# Shockley_EPS-v_2_0.net
KiCad netlist of a schematic drawn in EAGLE
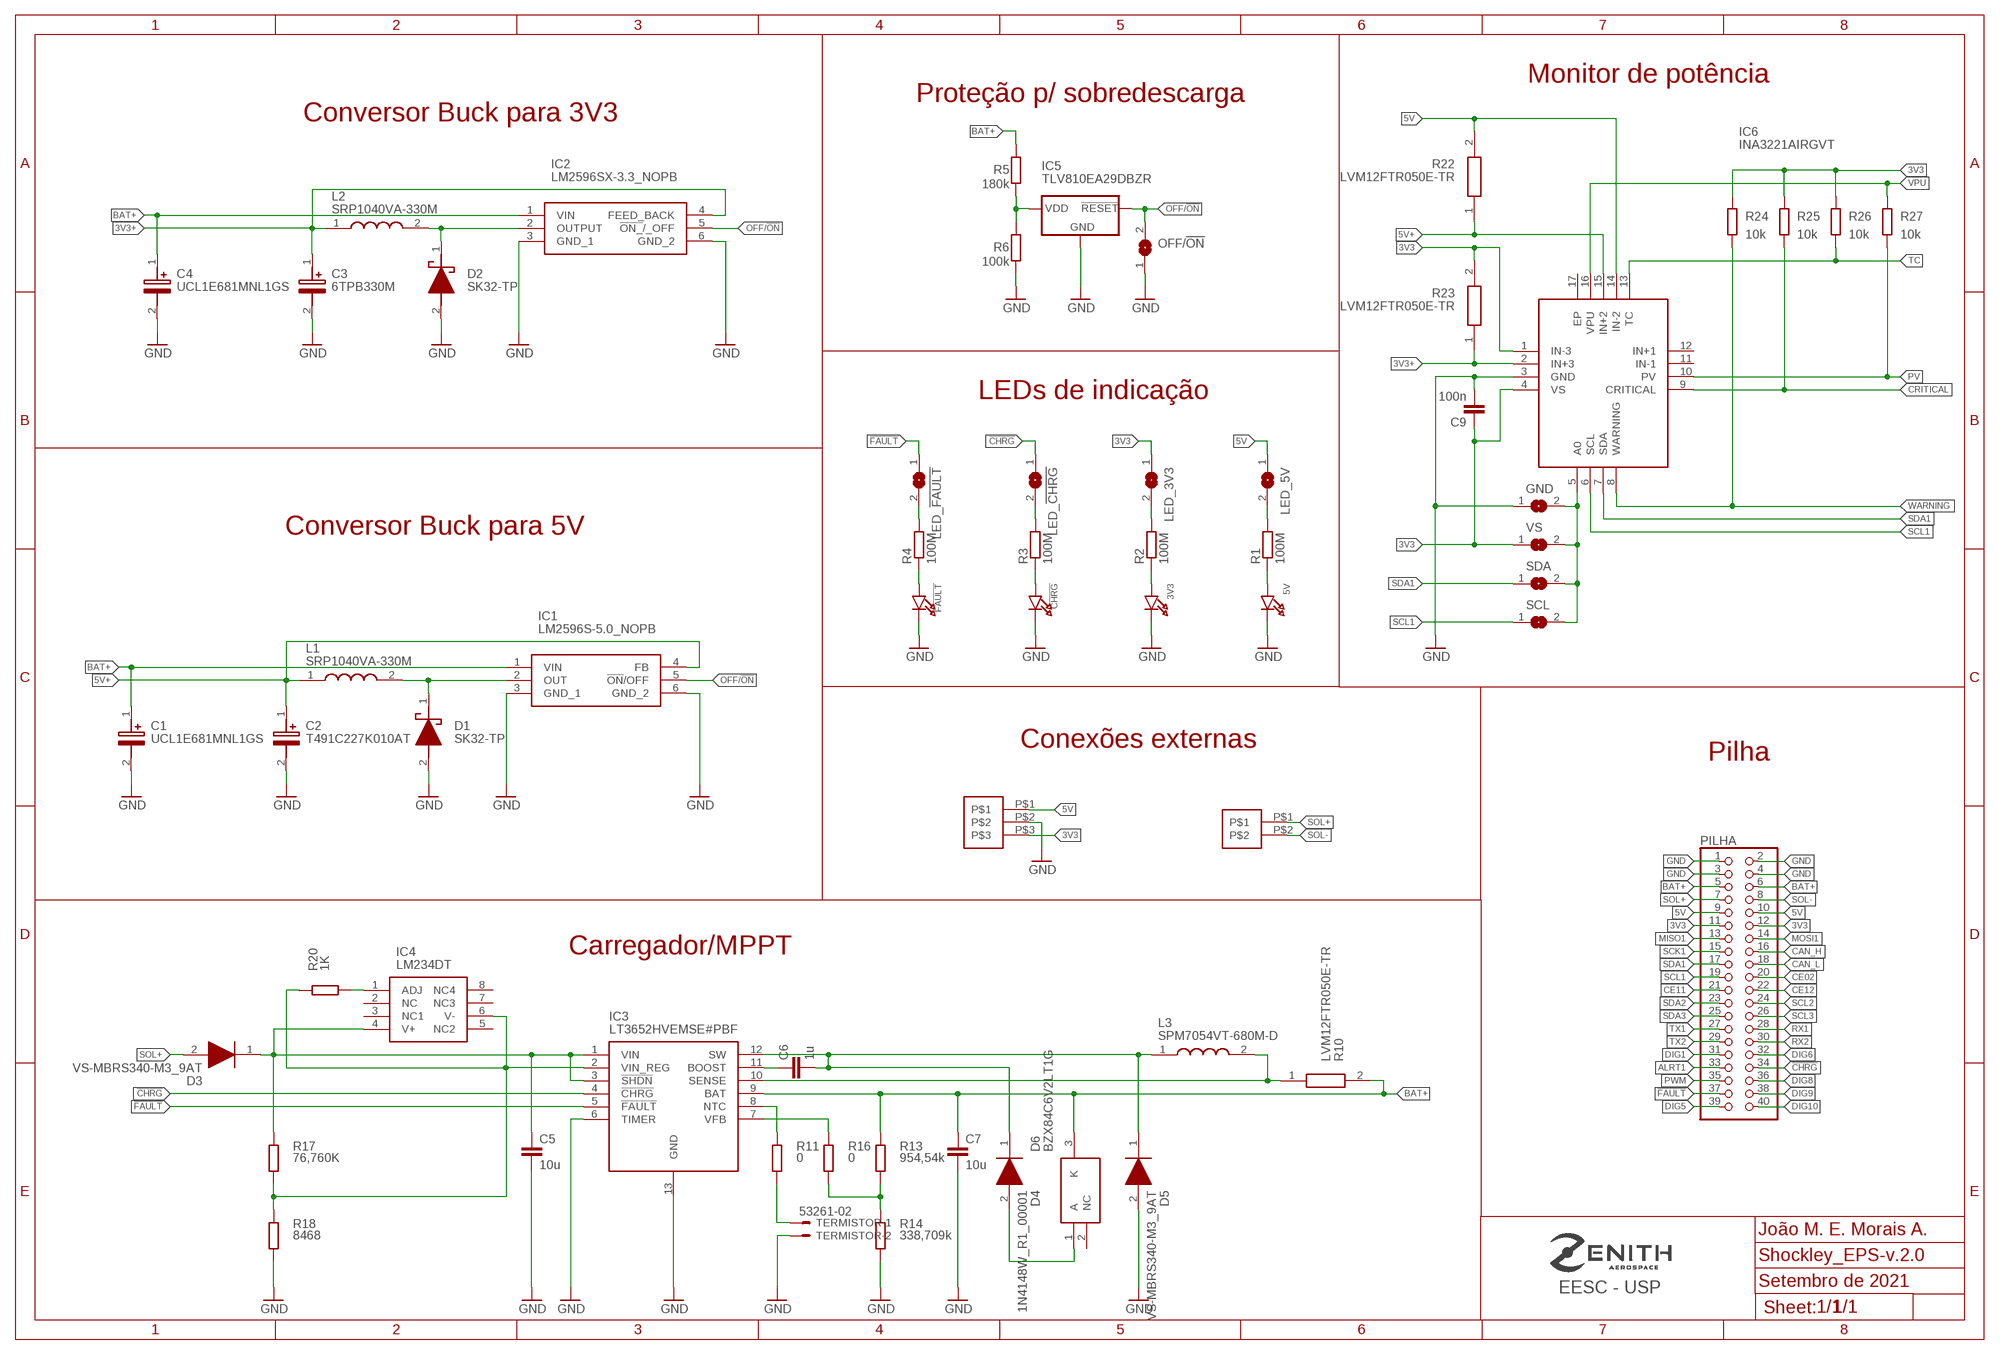
[diagram p0: schematic, sheet 1]

(export (version "E")
  (design (tool "Eeschema 10.0.6"))
  (components
    (comp (ref "!CHRG")
      (value "LED1206")
      (footprint "eagle-import:CHIPLED_1206")
      (libsource (lib "eagle-import") (part "LED1206"))
    )
    (comp (ref "!FAULT")
      (value "LED1206")
      (footprint "eagle-import:CHIPLED_1206")
      (libsource (lib "eagle-import") (part "LED1206"))
    )
    (comp (ref "3V3")
      (value "LED1206")
      (footprint "eagle-import:CHIPLED_1206")
      (libsource (lib "eagle-import") (part "LED1206"))
    )
    (comp (ref "5V")
      (value "LED1206")
      (footprint "eagle-import:CHIPLED_1206")
      (libsource (lib "eagle-import") (part "LED1206"))
    )
    (comp (ref "C1")
      (value "UCL1E681MNL1GS")
      (footprint "eagle-import:CAPAE1030X1400N")
      (fields (field (name "MOUSER_PART_NUMBER") "647-UCL1E681MNL1GS"))
      (libsource (lib "eagle-import") (part "UCL1E681MNL1GS"))
    )
    (comp (ref "C2")
      (value "T491C227K010AT")
      (footprint "eagle-import:CAPPM6032X280N")
      (fields (field (name "MOUSER_PART_NUMBER") "80-T491C227K010AT"))
      (libsource (lib "eagle-import") (part "T491C227K010AT"))
    )
    (comp (ref "C3")
      (value "6TPB330M")
      (footprint "eagle-import:10TPF150ML")
      (fields (field (name "MOUSER_PART_NUMBER") "667-6TPB330M"))
      (libsource (lib "eagle-import") (part "6TPB330M"))
    )
    (comp (ref "C4")
      (value "UCL1E681MNL1GS")
      (footprint "eagle-import:CAPAE1030X1400N")
      (fields (field (name "MOUSER_PART_NUMBER") "647-UCL1E681MNL1GS"))
      (libsource (lib "eagle-import") (part "UCL1E681MNL1GS"))
    )
    (comp (ref "C5")
      (value "10u")
      (footprint "eagle-import:C0805")
      (libsource (lib "eagle-import") (part "C-EUC0805"))
    )
    (comp (ref "C6")
      (value "1u")
      (footprint "eagle-import:C0805")
      (libsource (lib "eagle-import") (part "C-EUC0805"))
    )
    (comp (ref "C7")
      (value "10u")
      (footprint "eagle-import:C0805")
      (libsource (lib "eagle-import") (part "C-EUC0805"))
    )
    (comp (ref "C9")
      (value "100n")
      (footprint "eagle-import:C0805")
      (libsource (lib "eagle-import") (part "C-EUC0805"))
    )
    (comp (ref "D1")
      (value "SK32-TP")
      (footprint "eagle-import:DIOM7959X262N@1")
      (fields (field (name "MOUSER_PART_NUMBER") "833-SK32-TP"))
      (libsource (lib "eagle-import") (part "SK32-TP"))
    )
    (comp (ref "D2")
      (value "SK32-TP")
      (footprint "eagle-import:DIOM7959X262N@1")
      (fields (field (name "MOUSER_PART_NUMBER") "833-SK32-TP"))
      (libsource (lib "eagle-import") (part "SK32-TP"))
    )
    (comp (ref "D3")
      (value "VS-MBRS340-M3_9AT")
      (footprint "eagle-import:DIOM7959X262N")
      (fields
        (field (name "MANUFACTURER_PART_NUMBER") "VS-MBRS340-M3/9AT")
        (field (name "MOUSER_PART_NUMBER") "78-VS-MBRS340-M39AT")
      )
      (libsource (lib "eagle-import") (part "VS-MBRS340-M3_9AT"))
    )
    (comp (ref "D4")
      (value "1N4148W_R1_00001")
      (footprint "eagle-import:SOD3816X135N")
      (fields (field (name "MOUSER_PART_NUMBER") "241-1N4148W_R1_00001"))
      (libsource (lib "eagle-import") (part "1N4148W_R1_00001"))
    )
    (comp (ref "D5")
      (value "VS-MBRS340-M3_9AT")
      (footprint "eagle-import:DIOM7959X262N")
      (fields
        (field (name "MANUFACTURER_PART_NUMBER") "VS-MBRS340-M3/9AT")
        (field (name "MOUSER_PART_NUMBER") "78-VS-MBRS340-M39AT")
      )
      (libsource (lib "eagle-import") (part "VS-MBRS340-M3_9AT"))
    )
    (comp (ref "D6")
      (value "BZX84C6V2LT1G")
      (footprint "eagle-import:SOT96P237X111-3N")
      (fields (field (name "MOUSER_PART_NUMBER") "863-BZX84C6V2LT1G"))
      (libsource (lib "eagle-import") (part "BZX84C6V2LT1G"))
    )
    (comp (ref "GND")
      (value "SOLDERJUMPERREFLOW_NOPASTE")
      (footprint "eagle-import:SOLDERJUMPER_REFLOW_NOPASTE")
      (libsource (lib "eagle-import") (part "SOLDERJUMPERREFLOW_NOPASTE"))
    )
    (comp (ref "IC1")
      (value "LM2596S-5.0_NOPB")
      (footprint "eagle-import:KTT0005B")
      (fields
        (field (name "MANUFACTURER_PART_NUMBER") "LM2596S-5.0/NOPB")
        (field (name "MOUSER_PART_NUMBER") "926-LM2596S-5.0/NOPB")
      )
      (libsource (lib "eagle-import") (part "LM2596S-5.0_NOPB"))
    )
    (comp (ref "IC2")
      (value "LM2596SX-3.3_NOPB")
      (footprint "eagle-import:KTT0005B")
      (fields
        (field (name "MANUFACTURER_PART_NUMBER") "LM2596SX-3.3/NOPB")
        (field (name "MOUSER_PART_NUMBER") "926-LM2596SX33NOPB")
      )
      (libsource (lib "eagle-import") (part "LM2596SX-3.3_NOPB"))
    )
    (comp (ref "IC3")
      (value "LT3652HVEMSE#PBF")
      (footprint "eagle-import:SOP65P490X110-13N")
      (fields (field (name "MOUSER_PART_NUMBER") "584-LT3652HVEMSE#PBF"))
      (libsource (lib "eagle-import") (part "LT3652HVEMSE#PBF"))
    )
    (comp (ref "IC4")
      (value "LM234DT")
      (footprint "eagle-import:SOIC127P600X175-8N")
      (fields (field (name "MOUSER_PART_NUMBER") "511-LM234D"))
      (libsource (lib "eagle-import") (part "LM234DT"))
    )
    (comp (ref "IC5")
      (value "TLV810EA29DBZR")
      (footprint "eagle-import:SOT23")
      (libsource (lib "eagle-import") (part "TLV810EA29DBZR"))
    )
    (comp (ref "IC6")
      (value "INA3221AIRGVT")
      (footprint "eagle-import:QFN65P400X400X100-17N")
      (fields (field (name "MOUSER_PART_NUMBER") "595-INA3221AIRGVT"))
      (libsource (lib "eagle-import") (part "INA3221AIRGVT"))
    )
    (comp (ref "L1")
      (value "SRP1040VA-330M")
      (footprint "eagle-import:INDPM110100X400N")
      (fields (field (name "MOUSER_PART_NUMBER") "652-SRP1040VA-330M"))
      (libsource (lib "eagle-import") (part "SRP1040VA-330M"))
    )
    (comp (ref "L2")
      (value "SRP1040VA-330M")
      (footprint "eagle-import:INDPM110100X400N")
      (fields (field (name "MOUSER_PART_NUMBER") "652-SRP1040VA-330M"))
      (libsource (lib "eagle-import") (part "SRP1040VA-330M"))
    )
    (comp (ref "L3")
      (value "SPM7054VT-680M-D")
      (footprint "eagle-import:SPM7054VT")
      (fields (field (name "MOUSER_PART_NUMBER") "810-SPM7054VT-680M-D"))
      (libsource (lib "eagle-import") (part "SPM7054VT-680M-D"))
    )
    (comp (ref "LED_!CHRG")
      (value "SOLDERJUMPERREFLOW_NOPASTE")
      (footprint "eagle-import:SOLDERJUMPER_REFLOW_NOPASTE")
      (libsource (lib "eagle-import") (part "SOLDERJUMPERREFLOW_NOPASTE"))
    )
    (comp (ref "LED_!FAULT")
      (value "SOLDERJUMPERREFLOW_NOPASTE")
      (footprint "eagle-import:SOLDERJUMPER_REFLOW_NOPASTE")
      (libsource (lib "eagle-import") (part "SOLDERJUMPERREFLOW_NOPASTE"))
    )
    (comp (ref "LED_3V3")
      (value "SOLDERJUMPERREFLOW_NOPASTE")
      (footprint "eagle-import:SOLDERJUMPER_REFLOW_NOPASTE")
      (libsource (lib "eagle-import") (part "SOLDERJUMPERREFLOW_NOPASTE"))
    )
    (comp (ref "LED_5V")
      (value "SOLDERJUMPERREFLOW_NOPASTE")
      (footprint "eagle-import:SOLDERJUMPER_REFLOW_NOPASTE")
      (libsource (lib "eagle-import") (part "SOLDERJUMPERREFLOW_NOPASTE"))
    )
    (comp (ref "OFF/!ON")
      (value "SOLDERJUMPERREFLOW_NOPASTE")
      (footprint "eagle-import:SOLDERJUMPER_REFLOW_NOPASTE")
      (libsource (lib "eagle-import") (part "SOLDERJUMPERREFLOW_NOPASTE"))
    )
    (comp (ref "PILHA")
      (value "PINHD-2X20")
      (footprint "eagle-import:2X20")
      (libsource (lib "eagle-import") (part "PINHD-2X20"))
    )
    (comp (ref "R1")
      (value "100M")
      (footprint "eagle-import:R0805")
      (libsource (lib "eagle-import") (part "R-EU_R0805"))
    )
    (comp (ref "R2")
      (value "100M")
      (footprint "eagle-import:R0805")
      (libsource (lib "eagle-import") (part "R-EU_R0805"))
    )
    (comp (ref "R3")
      (value "100M")
      (footprint "eagle-import:R0805")
      (libsource (lib "eagle-import") (part "R-EU_R0805"))
    )
    (comp (ref "R4")
      (value "100M")
      (footprint "eagle-import:R0805")
      (libsource (lib "eagle-import") (part "R-EU_R0805"))
    )
    (comp (ref "R5")
      (value "180k")
      (footprint "eagle-import:R0805")
      (libsource (lib "eagle-import") (part "R-EU_R0805"))
    )
    (comp (ref "R6")
      (value "100k")
      (footprint "eagle-import:R0805")
      (libsource (lib "eagle-import") (part "R-EU_R0805"))
    )
    (comp (ref "R10")
      (value "LVM12FTR050E-TR")
      (footprint "eagle-import:RESC3016X70N")
      (fields (field (name "MOUSER_PART_NUMBER") "588-LVM12FTR050E-TR"))
      (libsource (lib "eagle-import") (part "LVM12FTR050E-TR"))
    )
    (comp (ref "R11")
      (value "0")
      (footprint "eagle-import:R0805")
      (libsource (lib "eagle-import") (part "R-EU_R0805"))
    )
    (comp (ref "R13")
      (value "954,54k")
      (footprint "eagle-import:R0805")
      (libsource (lib "eagle-import") (part "R-EU_R0805"))
    )
    (comp (ref "R14")
      (value "338,709k")
      (footprint "eagle-import:R0805")
      (libsource (lib "eagle-import") (part "R-EU_R0805"))
    )
    (comp (ref "R16")
      (value "0")
      (footprint "eagle-import:R0805")
      (libsource (lib "eagle-import") (part "R-EU_R0805"))
    )
    (comp (ref "R17")
      (value "76,760K")
      (footprint "eagle-import:R0805")
      (libsource (lib "eagle-import") (part "R-EU_R0805"))
    )
    (comp (ref "R18")
      (value "8468")
      (footprint "eagle-import:R0805")
      (libsource (lib "eagle-import") (part "R-EU_R0805"))
    )
    (comp (ref "R20")
      (value "1K")
      (footprint "eagle-import:R0805")
      (libsource (lib "eagle-import") (part "R-EU_R0805"))
    )
    (comp (ref "R22")
      (value "LVM12FTR050E-TR")
      (footprint "eagle-import:RESC3016X70N")
      (fields (field (name "MOUSER_PART_NUMBER") "588-LVM12FTR050E-TR"))
      (libsource (lib "eagle-import") (part "LVM12FTR050E-TR"))
    )
    (comp (ref "R23")
      (value "LVM12FTR050E-TR")
      (footprint "eagle-import:RESC3016X70N")
      (fields (field (name "MOUSER_PART_NUMBER") "588-LVM12FTR050E-TR"))
      (libsource (lib "eagle-import") (part "LVM12FTR050E-TR"))
    )
    (comp (ref "R24")
      (value "10k")
      (footprint "eagle-import:R0805")
      (libsource (lib "eagle-import") (part "R-EU_R0805"))
    )
    (comp (ref "R25")
      (value "10k")
      (footprint "eagle-import:R0805")
      (libsource (lib "eagle-import") (part "R-EU_R0805"))
    )
    (comp (ref "R26")
      (value "10k")
      (footprint "eagle-import:R0805")
      (libsource (lib "eagle-import") (part "R-EU_R0805"))
    )
    (comp (ref "R27")
      (value "10k")
      (footprint "eagle-import:R0805")
      (libsource (lib "eagle-import") (part "R-EU_R0805"))
    )
    (comp (ref "SCL")
      (value "SOLDERJUMPERREFLOW_NOPASTE")
      (footprint "eagle-import:SOLDERJUMPER_REFLOW_NOPASTE")
      (libsource (lib "eagle-import") (part "SOLDERJUMPERREFLOW_NOPASTE"))
    )
    (comp (ref "SDA")
      (value "SOLDERJUMPERREFLOW_NOPASTE")
      (footprint "eagle-import:SOLDERJUMPER_REFLOW_NOPASTE")
      (libsource (lib "eagle-import") (part "SOLDERJUMPERREFLOW_NOPASTE"))
    )
    (comp (ref "TERMISTOR")
      (value "53261-02")
      (footprint "eagle-import:53261-02")
      (fields (field (name "MF") "MOLEX"))
      (libsource (lib "eagle-import") (part "53?-02261"))
    )
    (comp (ref "U$1")
      (value "S02B-XASS-1")
      (footprint "eagle-import:S02B-XASS-1")
      (libsource (lib "eagle-import") (part "S02B-XASS-1"))
    )
    (comp (ref "U$2")
      (value "S03B-XASS-1")
      (footprint "eagle-import:S03B-XASS-1")
      (libsource (lib "eagle-import") (part "S03B-XASS-1"))
    )
    (comp (ref "VS")
      (value "SOLDERJUMPERREFLOW_NOPASTE")
      (footprint "eagle-import:SOLDERJUMPER_REFLOW_NOPASTE")
      (libsource (lib "eagle-import") (part "SOLDERJUMPERREFLOW_NOPASTE"))
    )
  )
  (nets
    (net (code "1") (name "/OFF{slash}~{ON}") (class "Default")
      (node (ref "IC1") (pin "5") (pinfunction "~{ON}/OFF_5") (pintype "bidirectional"))
      (node (ref "IC2") (pin "5") (pinfunction "~{ON_}/_OFF_5") (pintype "bidirectional"))
      (node (ref "IC5") (pin "1") (pinfunction "~{RESET}_1") (pintype "passive"))
      (node (ref "OFF/!ON") (pin "2") (pinfunction "2_2") (pintype "passive"))
    )
    (net (code "2") (name "/~{CHRG}") (class "Default")
      (node (ref "IC3") (pin "4") (pinfunction "~{CHRG}_4") (pintype "bidirectional"))
      (node (ref "LED_!CHRG") (pin "1") (pinfunction "1_1") (pintype "passive"))
      (node (ref "PILHA") (pin "34") (pinfunction "34_34") (pintype "passive"))
    )
    (net (code "3") (name "/~{FAULT}") (class "Default")
      (node (ref "IC3") (pin "5") (pinfunction "~{FAULT}_5") (pintype "bidirectional"))
      (node (ref "LED_!FAULT") (pin "1") (pinfunction "1_1") (pintype "passive"))
      (node (ref "PILHA") (pin "37") (pinfunction "37_37") (pintype "passive"))
    )
    (net (code "4") (name "3V3") (class "Default")
      (node (ref "C9") (pin "1") (pinfunction "1_1") (pintype "passive"))
      (node (ref "IC6") (pin "1") (pinfunction "IN-3_1") (pintype "bidirectional"))
      (node (ref "IC6") (pin "4") (pinfunction "VS_4") (pintype "bidirectional"))
      (node (ref "LED_3V3") (pin "1") (pinfunction "1_1") (pintype "passive"))
      (node (ref "PILHA") (pin "11") (pinfunction "11_11") (pintype "passive"))
      (node (ref "PILHA") (pin "12") (pinfunction "12_12") (pintype "passive"))
      (node (ref "R23") (pin "2") (pinfunction "2_2") (pintype "bidirectional"))
      (node (ref "R24") (pin "2") (pinfunction "2_2") (pintype "passive"))
      (node (ref "R25") (pin "2") (pinfunction "2_2") (pintype "passive"))
      (node (ref "R26") (pin "2") (pinfunction "2_2") (pintype "passive"))
      (node (ref "U$2") (pin "P$3") (pinfunction "P$3_P$3") (pintype "bidirectional"))
      (node (ref "VS") (pin "1") (pinfunction "1_1") (pintype "passive"))
    )
    (net (code "5") (name "3V3+") (class "Default")
      (node (ref "C3") (pin "1") (pinfunction "+_1") (pintype "bidirectional"))
      (node (ref "IC2") (pin "4") (pinfunction "FEED_BACK_4") (pintype "bidirectional"))
      (node (ref "IC6") (pin "2") (pinfunction "IN+3_2") (pintype "bidirectional"))
      (node (ref "L2") (pin "1") (pinfunction "1_1") (pintype "bidirectional"))
      (node (ref "R23") (pin "1") (pinfunction "1_1") (pintype "bidirectional"))
    )
    (net (code "6") (name "5V") (class "Default")
      (node (ref "IC6") (pin "14") (pinfunction "IN-2_14") (pintype "bidirectional"))
      (node (ref "LED_5V") (pin "1") (pinfunction "1_1") (pintype "passive"))
      (node (ref "PILHA") (pin "10") (pinfunction "10_10") (pintype "passive"))
      (node (ref "PILHA") (pin "9") (pinfunction "9_9") (pintype "passive"))
      (node (ref "R22") (pin "2") (pinfunction "2_2") (pintype "bidirectional"))
      (node (ref "U$2") (pin "P$1") (pinfunction "P$1_P$1") (pintype "bidirectional"))
    )
    (net (code "7") (name "5V+") (class "Default")
      (node (ref "C2") (pin "1") (pinfunction "+_1") (pintype "bidirectional"))
      (node (ref "IC1") (pin "4") (pinfunction "FB_4") (pintype "bidirectional"))
      (node (ref "IC6") (pin "15") (pinfunction "IN+2_15") (pintype "bidirectional"))
      (node (ref "L1") (pin "1") (pinfunction "1_1") (pintype "bidirectional"))
      (node (ref "R22") (pin "1") (pinfunction "1_1") (pintype "bidirectional"))
    )
    (net (code "8") (name "ALRT1") (class "Default")
      (node (ref "PILHA") (pin "33") (pinfunction "33_33") (pintype "passive"))
    )
    (net (code "9") (name "BAT+") (class "Default")
      (node (ref "C1") (pin "1") (pinfunction "+_1") (pintype "bidirectional"))
      (node (ref "C4") (pin "1") (pinfunction "+_1") (pintype "bidirectional"))
      (node (ref "C7") (pin "1") (pinfunction "1_1") (pintype "passive"))
      (node (ref "D6") (pin "3") (pinfunction "K_3") (pintype "bidirectional"))
      (node (ref "IC1") (pin "1") (pinfunction "VIN_1") (pintype "bidirectional"))
      (node (ref "IC2") (pin "1") (pinfunction "VIN_1") (pintype "bidirectional"))
      (node (ref "IC3") (pin "9") (pinfunction "BAT_9") (pintype "bidirectional"))
      (node (ref "PILHA") (pin "5") (pinfunction "5_5") (pintype "passive"))
      (node (ref "PILHA") (pin "6") (pinfunction "6_6") (pintype "passive"))
      (node (ref "R10") (pin "2") (pinfunction "2_2") (pintype "bidirectional"))
      (node (ref "R13") (pin "1") (pinfunction "1_1") (pintype "passive"))
      (node (ref "R5") (pin "1") (pinfunction "1_1") (pintype "passive"))
    )
    (net (code "10") (name "CAN_H") (class "Default")
      (node (ref "PILHA") (pin "16") (pinfunction "16_16") (pintype "passive"))
    )
    (net (code "11") (name "CAN_L") (class "Default")
      (node (ref "PILHA") (pin "18") (pinfunction "18_18") (pintype "passive"))
    )
    (net (code "12") (name "CE02") (class "Default")
      (node (ref "PILHA") (pin "20") (pinfunction "20_20") (pintype "passive"))
    )
    (net (code "13") (name "CE11") (class "Default")
      (node (ref "PILHA") (pin "21") (pinfunction "21_21") (pintype "passive"))
    )
    (net (code "14") (name "CE12") (class "Default")
      (node (ref "PILHA") (pin "22") (pinfunction "22_22") (pintype "passive"))
    )
    (net (code "15") (name "CRITICAL") (class "Default")
      (node (ref "IC6") (pin "9") (pinfunction "CRITICAL_9") (pintype "bidirectional"))
      (node (ref "R25") (pin "1") (pinfunction "1_1") (pintype "passive"))
    )
    (net (code "16") (name "DIG1") (class "Default")
      (node (ref "PILHA") (pin "31") (pinfunction "31_31") (pintype "passive"))
    )
    (net (code "17") (name "DIG5") (class "Default")
      (node (ref "PILHA") (pin "39") (pinfunction "39_39") (pintype "passive"))
    )
    (net (code "18") (name "DIG6") (class "Default")
      (node (ref "PILHA") (pin "32") (pinfunction "32_32") (pintype "passive"))
    )
    (net (code "19") (name "DIG8") (class "Default")
      (node (ref "PILHA") (pin "36") (pinfunction "36_36") (pintype "passive"))
    )
    (net (code "20") (name "DIG9") (class "Default")
      (node (ref "PILHA") (pin "38") (pinfunction "38_38") (pintype "passive"))
    )
    (net (code "21") (name "DIG10") (class "Default")
      (node (ref "PILHA") (pin "40") (pinfunction "40_40") (pintype "passive"))
    )
    (net (code "22") (name "GND") (class "Default")
      (node (ref "!CHRG") (pin "C") (pinfunction "C_C") (pintype "passive"))
      (node (ref "!FAULT") (pin "C") (pinfunction "C_C") (pintype "passive"))
      (node (ref "3V3") (pin "C") (pinfunction "C_C") (pintype "passive"))
      (node (ref "5V") (pin "C") (pinfunction "C_C") (pintype "passive"))
      (node (ref "C1") (pin "2") (pinfunction "-_2") (pintype "bidirectional"))
      (node (ref "C2") (pin "2") (pinfunction "-_2") (pintype "bidirectional"))
      (node (ref "C3") (pin "2") (pinfunction "-_2") (pintype "bidirectional"))
      (node (ref "C4") (pin "2") (pinfunction "-_2") (pintype "bidirectional"))
      (node (ref "C5") (pin "2") (pinfunction "2_2") (pintype "passive"))
      (node (ref "C7") (pin "2") (pinfunction "2_2") (pintype "passive"))
      (node (ref "C9") (pin "2") (pinfunction "2_2") (pintype "passive"))
      (node (ref "D1") (pin "2") (pinfunction "A_2") (pintype "bidirectional"))
      (node (ref "D2") (pin "2") (pinfunction "A_2") (pintype "bidirectional"))
      (node (ref "D5") (pin "2") (pinfunction "A_2") (pintype "bidirectional"))
      (node (ref "GND") (pin "1") (pinfunction "1_1") (pintype "passive"))
      (node (ref "IC1") (pin "3") (pinfunction "GND_1_3") (pintype "bidirectional"))
      (node (ref "IC1") (pin "6") (pinfunction "GND_2_6") (pintype "bidirectional"))
      (node (ref "IC2") (pin "3") (pinfunction "GND_1_3") (pintype "bidirectional"))
      (node (ref "IC2") (pin "6") (pinfunction "GND_2_6") (pintype "bidirectional"))
      (node (ref "IC3") (pin "13") (pinfunction "GND_13") (pintype "bidirectional"))
      (node (ref "IC3") (pin "6") (pinfunction "TIMER_6") (pintype "bidirectional"))
      (node (ref "IC5") (pin "2") (pinfunction "GND_2") (pintype "input"))
      (node (ref "IC6") (pin "3") (pinfunction "GND_3") (pintype "bidirectional"))
      (node (ref "OFF/!ON") (pin "1") (pinfunction "1_1") (pintype "passive"))
      (node (ref "PILHA") (pin "1") (pinfunction "1_1") (pintype "passive"))
      (node (ref "PILHA") (pin "2") (pinfunction "2_2") (pintype "passive"))
      (node (ref "PILHA") (pin "3") (pinfunction "3_3") (pintype "passive"))
      (node (ref "PILHA") (pin "4") (pinfunction "4_4") (pintype "passive"))
      (node (ref "R14") (pin "2") (pinfunction "2_2") (pintype "passive"))
      (node (ref "R18") (pin "2") (pinfunction "2_2") (pintype "passive"))
      (node (ref "R6") (pin "2") (pinfunction "2_2") (pintype "passive"))
      (node (ref "TERMISTOR") (pin "2") (pinfunction "S_2") (pintype "passive"))
      (node (ref "U$2") (pin "P$2") (pinfunction "P$2_P$2") (pintype "bidirectional"))
    )
    (net (code "23") (name "MISO1") (class "Default")
      (node (ref "PILHA") (pin "13") (pinfunction "13_13") (pintype "passive"))
    )
    (net (code "24") (name "MOSI1") (class "Default")
      (node (ref "PILHA") (pin "14") (pinfunction "14_14") (pintype "passive"))
    )
    (net (code "25") (name "Net-(!CHRG-PadA)") (class "Default")
      (node (ref "!CHRG") (pin "A") (pinfunction "A_A") (pintype "passive"))
      (node (ref "R3") (pin "1") (pinfunction "1_1") (pintype "passive"))
    )
    (net (code "26") (name "Net-(!FAULT-PadA)") (class "Default")
      (node (ref "!FAULT") (pin "A") (pinfunction "A_A") (pintype "passive"))
      (node (ref "R4") (pin "1") (pinfunction "1_1") (pintype "passive"))
    )
    (net (code "27") (name "Net-(3V3-PadA)") (class "Default")
      (node (ref "3V3") (pin "A") (pinfunction "A_A") (pintype "passive"))
      (node (ref "R2") (pin "1") (pinfunction "1_1") (pintype "passive"))
    )
    (net (code "28") (name "Net-(5V-PadA)") (class "Default")
      (node (ref "5V") (pin "A") (pinfunction "A_A") (pintype "passive"))
      (node (ref "R1") (pin "1") (pinfunction "1_1") (pintype "passive"))
    )
    (net (code "29") (name "Net-(D1-K)") (class "Default")
      (node (ref "D1") (pin "1") (pinfunction "K_1") (pintype "bidirectional"))
      (node (ref "IC1") (pin "2") (pinfunction "OUT_2") (pintype "bidirectional"))
      (node (ref "L1") (pin "2") (pinfunction "2_2") (pintype "bidirectional"))
    )
    (net (code "30") (name "Net-(D2-K)") (class "Default")
      (node (ref "D2") (pin "1") (pinfunction "K_1") (pintype "bidirectional"))
      (node (ref "IC2") (pin "2") (pinfunction "OUTPUT_2") (pintype "bidirectional"))
      (node (ref "L2") (pin "2") (pinfunction "2_2") (pintype "bidirectional"))
    )
    (net (code "31") (name "Net-(D3-K)") (class "Default")
      (node (ref "C5") (pin "1") (pinfunction "1_1") (pintype "passive"))
      (node (ref "D3") (pin "1") (pinfunction "K_1") (pintype "bidirectional"))
      (node (ref "IC3") (pin "1") (pinfunction "VIN_1") (pintype "bidirectional"))
      (node (ref "IC3") (pin "3") (pinfunction "~{SHDN}_3") (pintype "bidirectional"))
      (node (ref "IC4") (pin "4") (pinfunction "V+_4") (pintype "bidirectional"))
      (node (ref "R17") (pin "1") (pinfunction "1_1") (pintype "passive"))
    )
    (net (code "32") (name "Net-(D4-A)") (class "Default")
      (node (ref "D4") (pin "2") (pinfunction "A_2") (pintype "bidirectional"))
      (node (ref "D6") (pin "1") (pinfunction "A_1") (pintype "bidirectional"))
    )
    (net (code "33") (name "Net-(D4-K)") (class "Default")
      (node (ref "C6") (pin "2") (pinfunction "2_2") (pintype "passive"))
      (node (ref "D4") (pin "1") (pinfunction "K_1") (pintype "bidirectional"))
      (node (ref "D5") (pin "1") (pinfunction "K_1") (pintype "bidirectional"))
      (node (ref "IC3") (pin "12") (pinfunction "SW_12") (pintype "bidirectional"))
      (node (ref "L3") (pin "1") (pinfunction "1_1") (pintype "bidirectional"))
    )
    (net (code "34") (name "Net-(IC3-BOOST)") (class "Default")
      (node (ref "C6") (pin "1") (pinfunction "1_1") (pintype "passive"))
      (node (ref "IC3") (pin "11") (pinfunction "BOOST_11") (pintype "bidirectional"))
    )
    (net (code "35") (name "Net-(IC3-NTC)") (class "Default")
      (node (ref "IC3") (pin "8") (pinfunction "NTC_8") (pintype "bidirectional"))
      (node (ref "R11") (pin "1") (pinfunction "1_1") (pintype "passive"))
    )
    (net (code "36") (name "Net-(IC3-SENSE)") (class "Default")
      (node (ref "IC3") (pin "10") (pinfunction "SENSE_10") (pintype "bidirectional"))
      (node (ref "L3") (pin "2") (pinfunction "2_2") (pintype "bidirectional"))
      (node (ref "R10") (pin "1") (pinfunction "1_1") (pintype "bidirectional"))
    )
    (net (code "37") (name "Net-(IC3-VFB)") (class "Default")
      (node (ref "IC3") (pin "7") (pinfunction "VFB_7") (pintype "bidirectional"))
      (node (ref "R16") (pin "1") (pinfunction "1_1") (pintype "passive"))
    )
    (net (code "38") (name "Net-(IC3-VIN_REG)") (class "Default")
      (node (ref "IC3") (pin "2") (pinfunction "VIN_REG_2") (pintype "bidirectional"))
      (node (ref "IC4") (pin "6") (pinfunction "V-_6") (pintype "bidirectional"))
      (node (ref "R17") (pin "2") (pinfunction "2_2") (pintype "passive"))
      (node (ref "R18") (pin "1") (pinfunction "1_1") (pintype "passive"))
      (node (ref "R20") (pin "1") (pinfunction "1_1") (pintype "passive"))
    )
    (net (code "39") (name "Net-(IC4-ADJ)") (class "Default")
      (node (ref "IC4") (pin "1") (pinfunction "ADJ_1") (pintype "bidirectional"))
      (node (ref "R20") (pin "2") (pinfunction "2_2") (pintype "passive"))
    )
    (net (code "40") (name "Net-(IC5-VDD)") (class "Default")
      (node (ref "IC5") (pin "3") (pinfunction "VDD_3") (pintype "input"))
      (node (ref "R5") (pin "2") (pinfunction "2_2") (pintype "passive"))
      (node (ref "R6") (pin "1") (pinfunction "1_1") (pintype "passive"))
    )
    (net (code "41") (name "Net-(IC6-A0)") (class "Default")
      (node (ref "GND") (pin "2") (pinfunction "2_2") (pintype "passive"))
      (node (ref "IC6") (pin "5") (pinfunction "A0_5") (pintype "bidirectional"))
      (node (ref "SCL") (pin "2") (pinfunction "2_2") (pintype "passive"))
      (node (ref "SDA") (pin "2") (pinfunction "2_2") (pintype "passive"))
      (node (ref "VS") (pin "2") (pinfunction "2_2") (pintype "passive"))
    )
    (net (code "42") (name "Net-(LED_!CHRG-Pad2)") (class "Default")
      (node (ref "LED_!CHRG") (pin "2") (pinfunction "2_2") (pintype "passive"))
      (node (ref "R3") (pin "2") (pinfunction "2_2") (pintype "passive"))
    )
    (net (code "43") (name "Net-(LED_!FAULT-Pad2)") (class "Default")
      (node (ref "LED_!FAULT") (pin "2") (pinfunction "2_2") (pintype "passive"))
      (node (ref "R4") (pin "2") (pinfunction "2_2") (pintype "passive"))
    )
    (net (code "44") (name "Net-(LED_3V3-Pad2)") (class "Default")
      (node (ref "LED_3V3") (pin "2") (pinfunction "2_2") (pintype "passive"))
      (node (ref "R2") (pin "2") (pinfunction "2_2") (pintype "passive"))
    )
    (net (code "45") (name "Net-(LED_5V-Pad2)") (class "Default")
      (node (ref "LED_5V") (pin "2") (pinfunction "2_2") (pintype "passive"))
      (node (ref "R1") (pin "2") (pinfunction "2_2") (pintype "passive"))
    )
    (net (code "46") (name "Net-(R13-Pad2)") (class "Default")
      (node (ref "R13") (pin "2") (pinfunction "2_2") (pintype "passive"))
      (node (ref "R14") (pin "1") (pinfunction "1_1") (pintype "passive"))
      (node (ref "R16") (pin "2") (pinfunction "2_2") (pintype "passive"))
    )
    (net (code "47") (name "Net-(TERMISTORA-S)") (class "Default")
      (node (ref "R11") (pin "2") (pinfunction "2_2") (pintype "passive"))
      (node (ref "TERMISTOR") (pin "1") (pinfunction "S_1") (pintype "passive"))
    )
    (net (code "48") (name "PV") (class "Default")
      (node (ref "IC6") (pin "10") (pinfunction "PV_10") (pintype "bidirectional"))
      (node (ref "R27") (pin "1") (pinfunction "1_1") (pintype "passive"))
    )
    (net (code "49") (name "PWM") (class "Default")
      (node (ref "PILHA") (pin "35") (pinfunction "35_35") (pintype "passive"))
    )
    (net (code "50") (name "RX1") (class "Default")
      (node (ref "PILHA") (pin "28") (pinfunction "28_28") (pintype "passive"))
    )
    (net (code "51") (name "RX2") (class "Default")
      (node (ref "PILHA") (pin "30") (pinfunction "30_30") (pintype "passive"))
    )
    (net (code "52") (name "SCK1") (class "Default")
      (node (ref "PILHA") (pin "15") (pinfunction "15_15") (pintype "passive"))
    )
    (net (code "53") (name "SCL1") (class "Default")
      (node (ref "IC6") (pin "6") (pinfunction "SCL_6") (pintype "bidirectional"))
      (node (ref "PILHA") (pin "19") (pinfunction "19_19") (pintype "passive"))
      (node (ref "SCL") (pin "1") (pinfunction "1_1") (pintype "passive"))
    )
    (net (code "54") (name "SCL2") (class "Default")
      (node (ref "PILHA") (pin "24") (pinfunction "24_24") (pintype "passive"))
    )
    (net (code "55") (name "SCL3") (class "Default")
      (node (ref "PILHA") (pin "26") (pinfunction "26_26") (pintype "passive"))
    )
    (net (code "56") (name "SDA1") (class "Default")
      (node (ref "IC6") (pin "7") (pinfunction "SDA_7") (pintype "bidirectional"))
      (node (ref "PILHA") (pin "17") (pinfunction "17_17") (pintype "passive"))
      (node (ref "SDA") (pin "1") (pinfunction "1_1") (pintype "passive"))
    )
    (net (code "57") (name "SDA2") (class "Default")
      (node (ref "PILHA") (pin "23") (pinfunction "23_23") (pintype "passive"))
    )
    (net (code "58") (name "SDA3") (class "Default")
      (node (ref "PILHA") (pin "25") (pinfunction "25_25") (pintype "passive"))
    )
    (net (code "59") (name "SOL+") (class "Default")
      (node (ref "D3") (pin "2") (pinfunction "A_2") (pintype "bidirectional"))
      (node (ref "PILHA") (pin "7") (pinfunction "7_7") (pintype "passive"))
      (node (ref "U$1") (pin "P$1") (pinfunction "P$1_P$1") (pintype "bidirectional"))
    )
    (net (code "60") (name "SOL-") (class "Default")
      (node (ref "PILHA") (pin "8") (pinfunction "8_8") (pintype "passive"))
      (node (ref "U$1") (pin "P$2") (pinfunction "P$2_P$2") (pintype "bidirectional"))
    )
    (net (code "61") (name "TC") (class "Default")
      (node (ref "IC6") (pin "13") (pinfunction "TC_13") (pintype "bidirectional"))
      (node (ref "R26") (pin "1") (pinfunction "1_1") (pintype "passive"))
    )
    (net (code "62") (name "TX1") (class "Default")
      (node (ref "PILHA") (pin "27") (pinfunction "27_27") (pintype "passive"))
    )
    (net (code "63") (name "TX2") (class "Default")
      (node (ref "PILHA") (pin "29") (pinfunction "29_29") (pintype "passive"))
    )
    (net (code "64") (name "VPU") (class "Default")
      (node (ref "IC6") (pin "16") (pinfunction "VPU_16") (pintype "bidirectional"))
      (node (ref "R27") (pin "2") (pinfunction "2_2") (pintype "passive"))
    )
    (net (code "65") (name "WARNING") (class "Default")
      (node (ref "IC6") (pin "8") (pinfunction "WARNING_8") (pintype "bidirectional"))
      (node (ref "R24") (pin "1") (pinfunction "1_1") (pintype "passive"))
    )
    (net (code "66") (name "unconnected-(D6-NC-Pad2)") (class "Default")
      (node (ref "D6") (pin "2") (pinfunction "NC_2") (pintype "no_connect"))
    )
    (net (code "67") (name "unconnected-(IC4-NC-Pad2)") (class "Default")
      (node (ref "IC4") (pin "2") (pinfunction "NC_2") (pintype "no_connect"))
    )
    (net (code "68") (name "unconnected-(IC4-NC1-Pad3)") (class "Default")
      (node (ref "IC4") (pin "3") (pinfunction "NC1_3") (pintype "bidirectional"))
    )
    (net (code "69") (name "unconnected-(IC4-NC2-Pad5)") (class "Default")
      (node (ref "IC4") (pin "5") (pinfunction "NC2_5") (pintype "bidirectional"))
    )
    (net (code "70") (name "unconnected-(IC4-NC3-Pad7)") (class "Default")
      (node (ref "IC4") (pin "7") (pinfunction "NC3_7") (pintype "bidirectional"))
    )
    (net (code "71") (name "unconnected-(IC4-NC4-Pad8)") (class "Default")
      (node (ref "IC4") (pin "8") (pinfunction "NC4_8") (pintype "bidirectional"))
    )
    (net (code "72") (name "unconnected-(IC6-EP-Pad17)") (class "Default")
      (node (ref "IC6") (pin "17") (pinfunction "EP_17") (pintype "bidirectional"))
    )
    (net (code "73") (name "unconnected-(IC6-IN+1-Pad12)") (class "Default")
      (node (ref "IC6") (pin "12") (pinfunction "IN+1_12") (pintype "bidirectional"))
    )
    (net (code "74") (name "unconnected-(IC6-IN-1-Pad11)") (class "Default")
      (node (ref "IC6") (pin "11") (pinfunction "IN-1_11") (pintype "bidirectional"))
    )
  )
)
